# stirrer.net
KiCad netlist of a schematic drawn in EAGLE
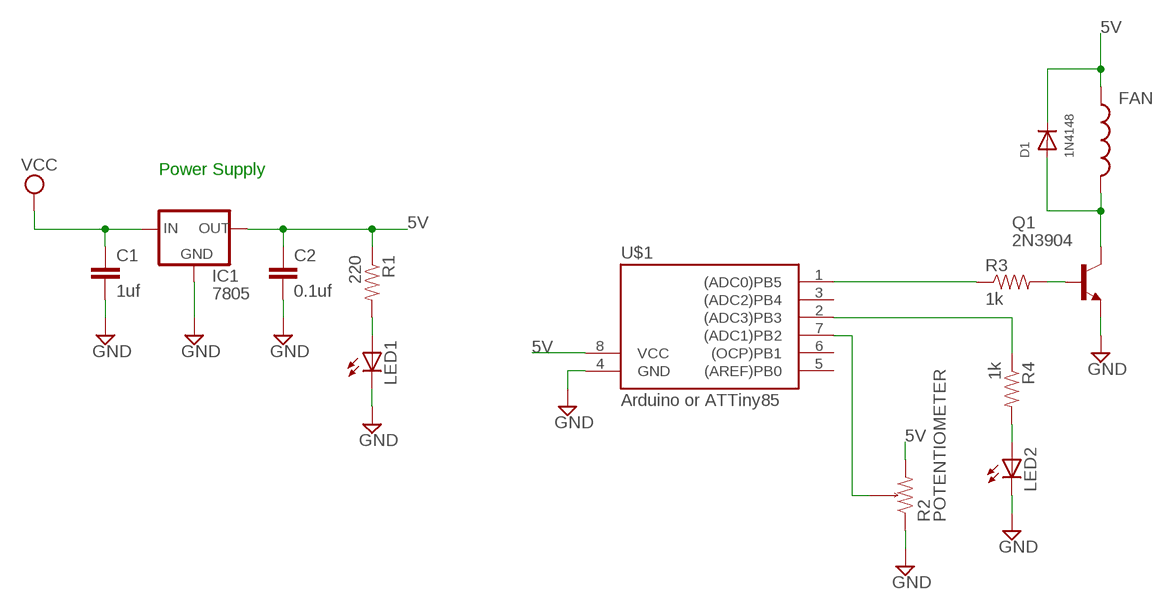
[diagram p0: schematic, sheet 1]

(export (version "E")
  (design (tool "Eeschema 10.0.6"))
  (components
    (comp (ref "C1")
      (value "1uf")
      (footprint "eagle-import:CAP-PTH-SMALL")
      (libsource (lib "eagle-import") (part "CAPPTH"))
    )
    (comp (ref "C2")
      (value "0.1uf")
      (footprint "eagle-import:CAP-PTH-SMALL")
      (libsource (lib "eagle-import") (part "CAPPTH"))
    )
    (comp (ref "D1")
      (value "1N4148")
      (footprint "eagle-import:DO-1N4148")
      (libsource (lib "eagle-import") (part "DIODEDO-1N4148"))
    )
    (comp (ref "FAN")
      (value "INDUCTOR-")
      (footprint "eagle-import:CDRH3D28")
      (libsource (lib "eagle-import") (part "INDUCTOR-"))
    )
    (comp (ref "IC1")
      (value "7805")
      (footprint "eagle-import:TO-220-ALT")
      (libsource (lib "eagle-import") (part "V_REG_78XX-TO-220"))
    )
    (comp (ref "LED1")
      (value "LED5MM")
      (footprint "eagle-import:LED5MM")
      (libsource (lib "eagle-import") (part "LED5MM"))
    )
    (comp (ref "LED2")
      (value "LED5MM")
      (footprint "eagle-import:LED5MM")
      (libsource (lib "eagle-import") (part "LED5MM"))
    )
    (comp (ref "Q1")
      (value "2N3904")
      (footprint "eagle-import:TO92")
      (libsource (lib "eagle-import") (part "2N3904"))
    )
    (comp (ref "R1")
      (value "220")
      (footprint "eagle-import:AXIAL-0.4")
      (libsource (lib "eagle-import") (part "RESISTORPTH-1/4W"))
    )
    (comp (ref "R2")
      (value "POTENTIOMETER")
      (footprint "eagle-import:0603-ARV")
      (libsource (lib "eagle-import") (part "POTENTIOMETER"))
    )
    (comp (ref "R3")
      (value "1k")
      (footprint "eagle-import:AXIAL-0.4")
      (libsource (lib "eagle-import") (part "RESISTORPTH-1/4W"))
    )
    (comp (ref "R4")
      (value "1k")
      (footprint "eagle-import:AXIAL-0.4")
      (libsource (lib "eagle-import") (part "RESISTORPTH-1/4W"))
    )
    (comp (ref "U$1")
      (value "Arduino or ATTiny85")
      (footprint "eagle-import:SOIC8")
      (libsource (lib "eagle-import") (part "TINY25/45/85-20SU"))
    )
  )
  (nets
    (net (code "1") (name "/5V") (class "Default")
      (node (ref "C2") (pin "1") (pinfunction "1_1") (pintype "passive"))
      (node (ref "D1") (pin "C") (pinfunction "C_C") (pintype "passive"))
      (node (ref "FAN") (pin "1") (pinfunction "1_1") (pintype "passive"))
      (node (ref "IC1") (pin "OUT") (pinfunction "OUT_OUT") (pintype "output"))
      (node (ref "R1") (pin "P$1") (pinfunction "1_P$1") (pintype "passive"))
      (node (ref "R2") (pin "2") (pinfunction "2_2") (pintype "passive"))
      (node (ref "U$1") (pin "8") (pinfunction "VCC_8") (pintype "power_in"))
    )
    (net (code "2") (name "GND") (class "Default")
      (node (ref "C1") (pin "2") (pinfunction "2_2") (pintype "passive"))
      (node (ref "C2") (pin "2") (pinfunction "2_2") (pintype "passive"))
      (node (ref "IC1") (pin "GND") (pinfunction "GND_GND") (pintype "input"))
      (node (ref "LED1") (pin "K") (pinfunction "C_K") (pintype "passive"))
      (node (ref "LED2") (pin "K") (pinfunction "C_K") (pintype "passive"))
      (node (ref "Q1") (pin "3") (pinfunction "E_3") (pintype "passive"))
      (node (ref "R2") (pin "1") (pinfunction "1_1") (pintype "passive"))
      (node (ref "U$1") (pin "4") (pinfunction "GND_4") (pintype "power_in"))
    )
    (net (code "3") (name "Net-(Q1-B)") (class "Default")
      (node (ref "Q1") (pin "2") (pinfunction "B_2") (pintype "passive"))
      (node (ref "R3") (pin "P$2") (pinfunction "2_P$2") (pintype "passive"))
    )
    (net (code "4") (name "Net-(Q1-C)") (class "Default")
      (node (ref "D1") (pin "A") (pinfunction "A_A") (pintype "passive"))
      (node (ref "FAN") (pin "2") (pinfunction "2_2") (pintype "passive"))
      (node (ref "Q1") (pin "1") (pinfunction "C_1") (pintype "passive"))
    )
    (net (code "5") (name "Net-(R1-2)") (class "Default")
      (node (ref "LED1") (pin "A") (pinfunction "A_A") (pintype "passive"))
      (node (ref "R1") (pin "P$2") (pinfunction "2_P$2") (pintype "passive"))
    )
    (net (code "6") (name "Net-(R3-1)") (class "Default")
      (node (ref "R3") (pin "P$1") (pinfunction "1_P$1") (pintype "passive"))
      (node (ref "U$1") (pin "1") (pinfunction "(ADC0)PB5_1") (pintype "bidirectional"))
    )
    (net (code "7") (name "Net-(R4-1)") (class "Default")
      (node (ref "R4") (pin "P$1") (pinfunction "1_P$1") (pintype "passive"))
      (node (ref "U$1") (pin "2") (pinfunction "(ADC3)PB3_2") (pintype "bidirectional"))
    )
    (net (code "8") (name "Net-(R4-2)") (class "Default")
      (node (ref "LED2") (pin "A") (pinfunction "A_A") (pintype "passive"))
      (node (ref "R4") (pin "P$2") (pinfunction "2_P$2") (pintype "passive"))
    )
    (net (code "9") (name "Net-(U$1-(ADC1)PB2)") (class "Default")
      (node (ref "R2") (pin "3") (pinfunction "P$1_3") (pintype "bidirectional"))
      (node (ref "R2") (pin "4") (pinfunction "P$1_4") (pintype "bidirectional"))
      (node (ref "R2") (pin "5") (pinfunction "P$1_5") (pintype "bidirectional"))
      (node (ref "R2") (pin "6") (pinfunction "P$1_6") (pintype "bidirectional"))
      (node (ref "R2") (pin "7") (pinfunction "P$1_7") (pintype "bidirectional"))
      (node (ref "R2") (pin "8") (pinfunction "P$1_8") (pintype "bidirectional"))
      (node (ref "U$1") (pin "7") (pinfunction "(ADC1)PB2_7") (pintype "bidirectional"))
    )
    (net (code "10") (name "VCC") (class "Default")
      (node (ref "C1") (pin "1") (pinfunction "1_1") (pintype "passive"))
      (node (ref "IC1") (pin "IN") (pinfunction "IN_IN") (pintype "input"))
    )
    (net (code "11") (name "unconnected-(U$1-(ADC2)PB4-Pad3)") (class "Default")
      (node (ref "U$1") (pin "3") (pinfunction "(ADC2)PB4_3") (pintype "bidirectional"))
    )
    (net (code "12") (name "unconnected-(U$1-(AREF)PB0-Pad5)") (class "Default")
      (node (ref "U$1") (pin "5") (pinfunction "(AREF)PB0_5") (pintype "bidirectional"))
    )
    (net (code "13") (name "unconnected-(U$1-(OCP)PB1-Pad6)") (class "Default")
      (node (ref "U$1") (pin "6") (pinfunction "(OCP)PB1_6") (pintype "bidirectional"))
    )
  )
)
